# SchemeAcSensor.net
KiCad netlist of a schematic drawn in Altium Designer
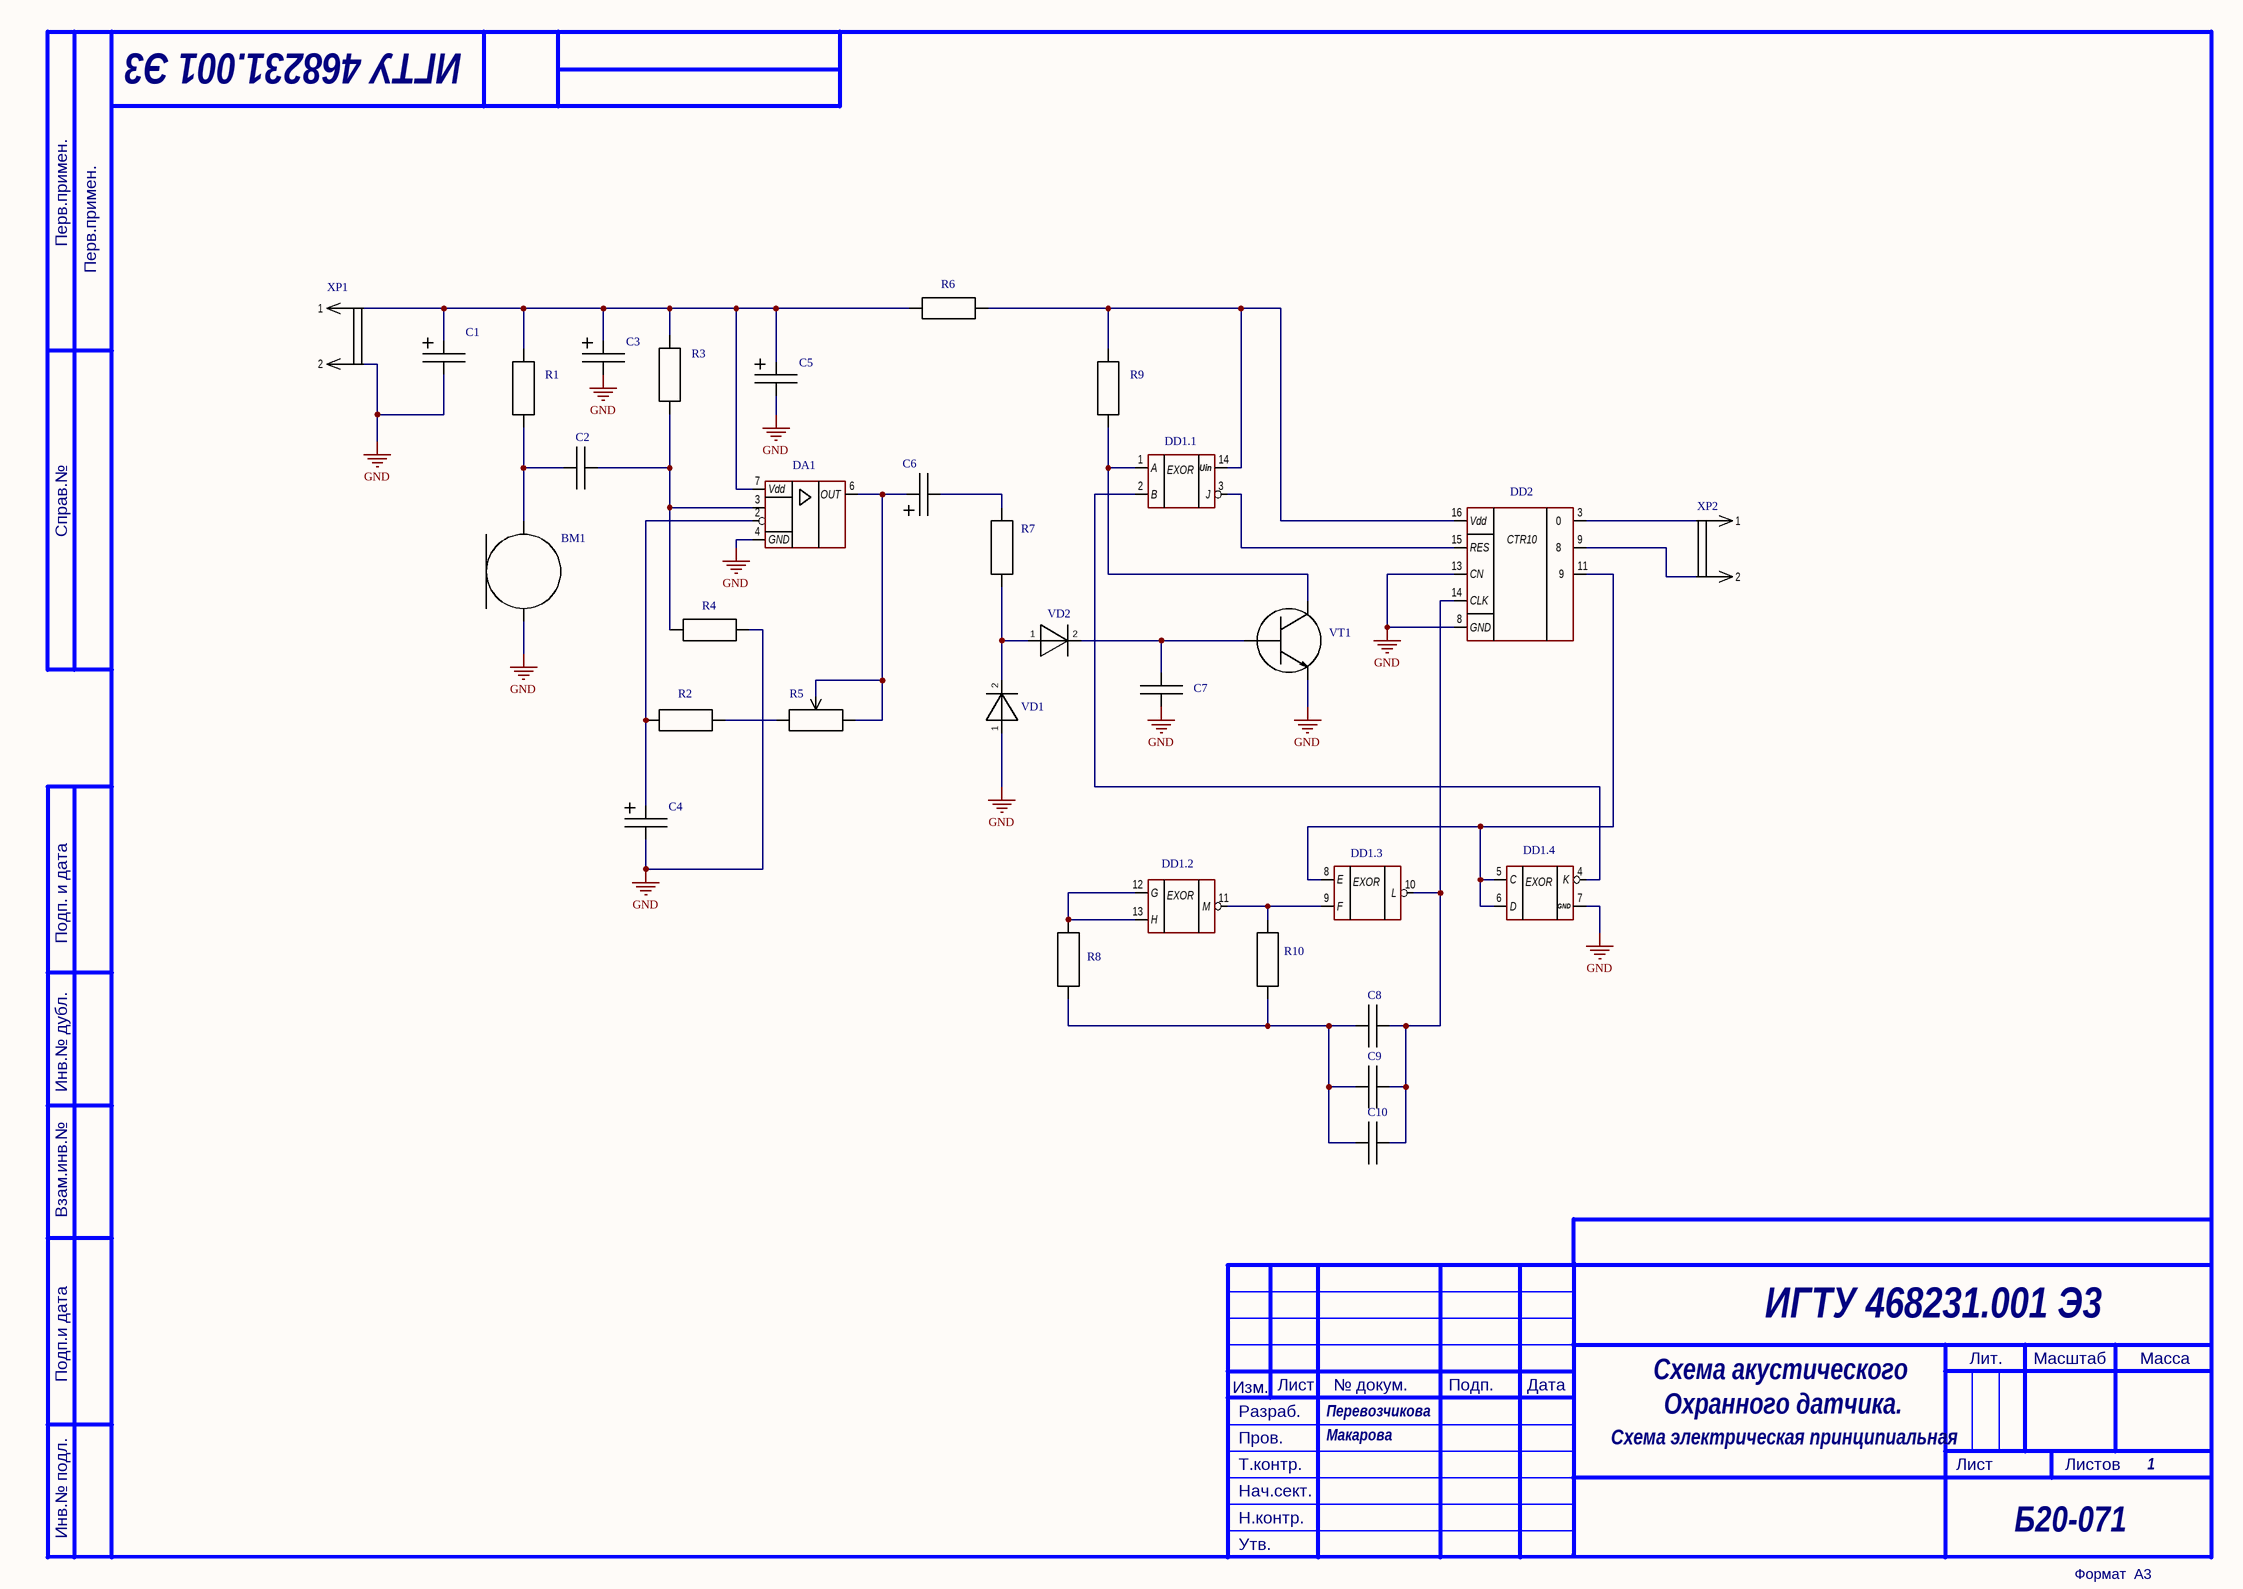
[diagram p0: SchemeAcSensor.SchDoc]

(export (version "E")
  (design (tool "Eeschema 10.0.6"))
  (components
    (comp (ref "BM1") (value "Micro") (footprint "electret_micro") (libsource (lib "Schlib2") (part "Micro")))
    (comp (ref "C1")
      (value "470 mF")
      (footprint "CAPA_Polar")
      (libsource (lib "Schlib2") (part "Capacitor_polar"))
    )
    (comp (ref "C2")
      (value "Capacitor")
      (footprint "CAPA_1206")
      (libsource (lib "Schlib2") (part "Capacitor"))
    )
    (comp (ref "C3")
      (value "Capacitor_polar")
      (footprint "CAPA_К50-35")
      (libsource (lib "Schlib2") (part "Capacitor_polar"))
    )
    (comp (ref "C4")
      (value "Capacitor_polar")
      (footprint "CAPA_К50-35")
      (libsource (lib "Schlib2") (part "Capacitor_polar"))
    )
    (comp (ref "C5")
      (value "Capacitor_polar")
      (footprint "CAPA_К50-35")
      (libsource (lib "Schlib2") (part "Capacitor_polar"))
    )
    (comp (ref "C6")
      (value "Capacitor_polar")
      (footprint "CAPA_К50-35")
      (libsource (lib "Schlib2") (part "Capacitor_polar"))
    )
    (comp (ref "C7")
      (value "Capacitor")
      (footprint "CAPA_1206")
      (libsource (lib "Schlib2") (part "Capacitor"))
    )
    (comp (ref "C8")
      (value "Capacitor")
      (footprint "CAPA_1206")
      (libsource (lib "Schlib2") (part "Capacitor"))
    )
    (comp (ref "C9")
      (value "Capacitor")
      (footprint "CAPA_1206")
      (libsource (lib "Schlib2") (part "Capacitor"))
    )
    (comp (ref "C10")
      (value "Capacitor")
      (footprint "CAPA_1206")
      (libsource (lib "Schlib2") (part "Capacitor"))
    )
    (comp (ref "DA1")
      (value "OperationalAmplifire")
      (footprint "OPERATION_AMPLIFIRE")
      (libsource (lib "Schlib2") (part "OperationalAmplifire"))
    )
    (comp (ref "DD1") (value "DD1.1") (footprint "CD4001B_DIP") (libsource (lib "Schlib2") (part "CD4001B")))
    (comp (ref "DD2") (value "CD4017") (footprint "CB4017B") (libsource (lib "Schlib2") (part "CD4017")))
    (comp (ref "R1") (value "Res") (footprint "RES0805") (libsource (lib "") (part "Res_1")))
    (comp (ref "R2") (value "Res") (footprint "RES0805") (libsource (lib "") (part "Res_2")))
    (comp (ref "R3") (value "Res") (footprint "RES0805") (libsource (lib "") (part "Res_1")))
    (comp (ref "R4") (value "Res") (footprint "RES0805") (libsource (lib "Schlib2") (part "Res")))
    (comp (ref "R5")
      (value "Potentiometer")
      (footprint "POTENTIOMETER")
      (libsource (lib "Schlib2") (part "Potentiometer"))
    )
    (comp (ref "R6") (value "Res") (footprint "RES0805") (libsource (lib "Schlib2") (part "Res")))
    (comp (ref "R7") (value "Res") (footprint "RES0805") (libsource (lib "") (part "Res_1")))
    (comp (ref "R8") (value "Res") (footprint "RES0805") (libsource (lib "") (part "Res_1")))
    (comp (ref "R9") (value "Res") (footprint "RES0805") (libsource (lib "") (part "Res_1")))
    (comp (ref "R10") (value "Res") (footprint "RES_output") (libsource (lib "") (part "Res_1")))
    (comp (ref "VD1") (value "Diod") (footprint "DIODE") (libsource (lib "Schlib2") (part "Diod")))
    (comp (ref "VD2") (value "Diod") (footprint "DIODE") (libsource (lib "Schlib2") (part "Diod")))
    (comp (ref "VT1") (value "NPN") (footprint "TRANSISTOR_KT3102") (libsource (lib "Schlib2") (part "NPN")))
    (comp (ref "XP1")
      (value "InputOutput")
      (footprint "INPUT_OUTPUT_CWF-2R")
      (libsource (lib "Schlib2") (part "InputOutput"))
    )
    (comp (ref "XP2")
      (value "InputOutput")
      (footprint "INPUT_OUTPUT_CWF-2R")
      (libsource (lib "Schlib2") (part "InputOutput"))
    )
  )
  (nets
    (net (code "1") (name "GND") (class "Default")
      (node (ref "BM1") (pin "1") (pinfunction "1_1") (pintype "passive"))
      (node (ref "C1") (pin "1") (pinfunction "1_1") (pintype "passive"))
      (node (ref "C3") (pin "1") (pinfunction "1_1") (pintype "passive"))
      (node (ref "C4") (pin "1") (pinfunction "1_1") (pintype "passive"))
      (node (ref "C5") (pin "1") (pinfunction "1_1") (pintype "passive"))
      (node (ref "C7") (pin "1") (pinfunction "1_1") (pintype "passive"))
      (node (ref "DA1") (pin "4") (pinfunction "GND_4") (pintype "passive"))
      (node (ref "DD1") (pin "7") (pinfunction "GND_7") (pintype "passive"))
      (node (ref "DD2") (pin "13") (pinfunction "CN_13") (pintype "passive"))
      (node (ref "DD2") (pin "8") (pinfunction "GND_8") (pintype "passive"))
      (node (ref "R4") (pin "1") (pinfunction "_1_1") (pintype "passive"))
      (node (ref "VD1") (pin "1") (pinfunction "1_1") (pintype "passive"))
      (node (ref "VT1") (pin "3") (pinfunction "3_3") (pintype "passive"))
      (node (ref "XP1") (pin "2") (pinfunction "2_2") (pintype "passive"))
    )
    (net (code "2") (name "Net-(C7-Pad2)") (class "Default")
      (node (ref "C7") (pin "2") (pinfunction "2_2") (pintype "passive"))
      (node (ref "VD2") (pin "2") (pinfunction "2_2") (pintype "passive"))
      (node (ref "VT1") (pin "1") (pinfunction "1_1") (pintype "passive"))
    )
    (net (code "3") (name "Net-(DA1-OUT)") (class "Default")
      (node (ref "C6") (pin "2") (pinfunction "2_2") (pintype "passive"))
      (node (ref "DA1") (pin "6") (pinfunction "OUT_6") (pintype "passive"))
      (node (ref "R5") (pin "2") (pinfunction "_2_2") (pintype "passive"))
      (node (ref "R5") (pin "3") (pinfunction "3_3") (pintype "passive"))
    )
    (net (code "4") (name "Net-(DA1-Vdd)") (class "Default")
      (node (ref "C1") (pin "2") (pinfunction "2_2") (pintype "passive"))
      (node (ref "C3") (pin "2") (pinfunction "2_2") (pintype "passive"))
      (node (ref "C5") (pin "2") (pinfunction "2_2") (pintype "passive"))
      (node (ref "DA1") (pin "7") (pinfunction "Vdd_7") (pintype "passive"))
      (node (ref "R1") (pin "2") (pinfunction "_2_2") (pintype "passive"))
      (node (ref "R3") (pin "2") (pinfunction "_2_2") (pintype "passive"))
      (node (ref "R6") (pin "2") (pinfunction "_2_2") (pintype "passive"))
      (node (ref "XP1") (pin "1") (pinfunction "1_1") (pintype "passive"))
    )
    (net (code "5") (name "Net-(DD1A-A)") (class "Default")
      (node (ref "DD1") (pin "1") (pinfunction "A_1") (pintype "passive"))
      (node (ref "R9") (pin "1") (pinfunction "_1_1") (pintype "passive"))
      (node (ref "VT1") (pin "2") (pinfunction "2_2") (pintype "passive"))
    )
    (net (code "6") (name "Net-(DD1A-B)") (class "Default")
      (node (ref "DD1") (pin "2") (pinfunction "B_2") (pintype "passive"))
      (node (ref "DD1") (pin "4") (pinfunction "K_4") (pintype "passive"))
    )
    (net (code "7") (name "Net-(DD1A-J)") (class "Default")
      (node (ref "DD1") (pin "3") (pinfunction "J_3") (pintype "passive"))
      (node (ref "DD2") (pin "15") (pinfunction "RES_15") (pintype "passive"))
    )
    (net (code "8") (name "Net-(DD1A-Uin)") (class "Default")
      (node (ref "DD1") (pin "14") (pinfunction "Uin_14") (pintype "passive"))
      (node (ref "DD2") (pin "16") (pinfunction "Vdd_16") (pintype "passive"))
      (node (ref "R6") (pin "1") (pinfunction "_1_1") (pintype "passive"))
      (node (ref "R9") (pin "2") (pinfunction "_2_2") (pintype "passive"))
    )
    (net (code "9") (name "Net-(DD1B-G)") (class "Default")
      (node (ref "DD1") (pin "12") (pinfunction "G_12") (pintype "passive"))
      (node (ref "DD1") (pin "13") (pinfunction "H_13") (pintype "passive"))
      (node (ref "R8") (pin "2") (pinfunction "_2_2") (pintype "passive"))
    )
    (net (code "10") (name "Net-(DD1B-M)") (class "Default")
      (node (ref "DD1") (pin "11") (pinfunction "M_11") (pintype "passive"))
      (node (ref "DD1") (pin "9") (pinfunction "F_9") (pintype "passive"))
      (node (ref "R10") (pin "2") (pinfunction "_2_2") (pintype "passive"))
    )
    (net (code "11") (name "Net-(DD1C-E)") (class "Default")
      (node (ref "DD1") (pin "5") (pinfunction "C_5") (pintype "passive"))
      (node (ref "DD1") (pin "6") (pinfunction "D_6") (pintype "passive"))
      (node (ref "DD1") (pin "8") (pinfunction "E_8") (pintype "passive"))
      (node (ref "DD2") (pin "11") (pinfunction "9_11") (pintype "passive"))
    )
    (net (code "12") (name "Net-(DD1C-L)") (class "Default")
      (node (ref "C10") (pin "2") (pinfunction "2_2") (pintype "passive"))
      (node (ref "C8") (pin "2") (pinfunction "2_2") (pintype "passive"))
      (node (ref "C9") (pin "2") (pinfunction "2_2") (pintype "passive"))
      (node (ref "DD1") (pin "10") (pinfunction "L_10") (pintype "passive"))
      (node (ref "DD2") (pin "14") (pinfunction "CLK_14") (pintype "passive"))
    )
    (net (code "13") (name "Net-(DD2-0)") (class "Default")
      (node (ref "DD2") (pin "3") (pinfunction "0_3") (pintype "passive"))
      (node (ref "XP2") (pin "1") (pinfunction "1_1") (pintype "passive"))
    )
    (net (code "14") (name "Net-(DD2-8)") (class "Default")
      (node (ref "DD2") (pin "9") (pinfunction "8_9") (pintype "passive"))
      (node (ref "XP2") (pin "2") (pinfunction "2_2") (pintype "passive"))
    )
    (net (code "15") (name "Net-(R1-_1)") (class "Default")
      (node (ref "BM1") (pin "2") (pinfunction "2_2") (pintype "passive"))
      (node (ref "C2") (pin "1") (pinfunction "1_1") (pintype "passive"))
      (node (ref "R1") (pin "1") (pinfunction "_1_1") (pintype "passive"))
    )
    (net (code "16") (name "Net-(R2-_1)") (class "Default")
      (node (ref "C4") (pin "2") (pinfunction "2_2") (pintype "passive"))
      (node (ref "DA1") (pin "2") (pintype "passive"))
      (node (ref "R2") (pin "1") (pinfunction "_1_1") (pintype "passive"))
    )
    (net (code "17") (name "Net-(R2-_2)") (class "Default")
      (node (ref "R2") (pin "2") (pinfunction "_2_2") (pintype "passive"))
      (node (ref "R5") (pin "1") (pinfunction "_1_1") (pintype "passive"))
    )
    (net (code "18") (name "Net-(R3-_1)") (class "Default")
      (node (ref "C2") (pin "2") (pinfunction "2_2") (pintype "passive"))
      (node (ref "DA1") (pin "3") (pintype "passive"))
      (node (ref "R3") (pin "1") (pinfunction "_1_1") (pintype "passive"))
      (node (ref "R4") (pin "2") (pinfunction "_2_2") (pintype "passive"))
    )
    (net (code "19") (name "Net-(R7-_1)") (class "Default")
      (node (ref "R7") (pin "1") (pinfunction "_1_1") (pintype "passive"))
      (node (ref "VD1") (pin "2") (pinfunction "2_2") (pintype "passive"))
      (node (ref "VD2") (pin "1") (pinfunction "1_1") (pintype "passive"))
    )
    (net (code "20") (name "Net-(R7-_2)") (class "Default")
      (node (ref "C6") (pin "1") (pinfunction "1_1") (pintype "passive"))
      (node (ref "R7") (pin "2") (pinfunction "_2_2") (pintype "passive"))
    )
    (net (code "21") (name "Net-(R10-_1)") (class "Default")
      (node (ref "C10") (pin "1") (pinfunction "1_1") (pintype "passive"))
      (node (ref "C8") (pin "1") (pinfunction "1_1") (pintype "passive"))
      (node (ref "C9") (pin "1") (pinfunction "1_1") (pintype "passive"))
      (node (ref "R10") (pin "1") (pinfunction "_1_1") (pintype "passive"))
      (node (ref "R8") (pin "1") (pinfunction "_1_1") (pintype "passive"))
    )
  )
)
